# 05-AD8412.net
KiCad netlist of a schematic drawn in Altium Designer
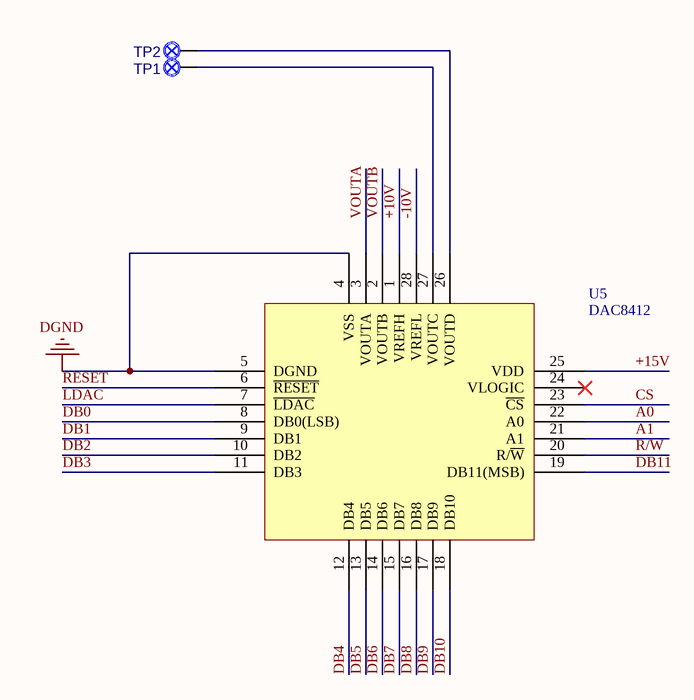
[diagram p0: 05-AD8412.SchDoc]

(export (version "E")
  (design (tool "Eeschema 10.0.6"))
  (components
    (comp (ref "TP1") (value "TESTPOINT") (footprint "TP24-SMD") (libsource (lib "*") (part "TESTPOINT_0")))
    (comp (ref "TP2") (value "TESTPOINT") (footprint "TP24-SMD") (libsource (lib "*") (part "TESTPOINT_0")))
    (comp (ref "U5")
      (value "DAC8412")
      (footprint "PLCC-28_L11.5-W11.5-P1.27-LS12.5-L")
      (libsource (lib "sucaiku") (part "DAC8412"))
    )
  )
  (nets
    (net (code "1") (name "/+10V") (class "Default")
      (node (ref "U5") (pin "1") (pinfunction "VREFH_1") (pintype "passive"))
    )
    (net (code "2") (name "/+15V") (class "Default")
      (node (ref "U5") (pin "25") (pinfunction "VDD_25") (pintype "passive"))
    )
    (net (code "3") (name "/-10V") (class "Default")
      (node (ref "U5") (pin "28") (pinfunction "VREFL_28") (pintype "passive"))
    )
    (net (code "4") (name "/A0") (class "Default")
      (node (ref "U5") (pin "22") (pinfunction "A0_22") (pintype "passive"))
    )
    (net (code "5") (name "/A1") (class "Default")
      (node (ref "U5") (pin "21") (pinfunction "A1_21") (pintype "passive"))
    )
    (net (code "6") (name "/CS") (class "Default")
      (node (ref "U5") (pin "23") (pinfunction "~{CS}_23") (pintype "passive"))
    )
    (net (code "7") (name "/DB0") (class "Default")
      (node (ref "U5") (pin "8") (pinfunction "DB0(LSB)_8") (pintype "passive"))
    )
    (net (code "8") (name "/DB1") (class "Default")
      (node (ref "U5") (pin "9") (pinfunction "DB1_9") (pintype "passive"))
    )
    (net (code "9") (name "/DB2") (class "Default")
      (node (ref "U5") (pin "10") (pinfunction "DB2_10") (pintype "passive"))
    )
    (net (code "10") (name "/DB3") (class "Default")
      (node (ref "U5") (pin "11") (pinfunction "DB3_11") (pintype "passive"))
    )
    (net (code "11") (name "/DB4") (class "Default")
      (node (ref "U5") (pin "12") (pinfunction "DB4_12") (pintype "passive"))
    )
    (net (code "12") (name "/DB5") (class "Default")
      (node (ref "U5") (pin "13") (pinfunction "DB5_13") (pintype "passive"))
    )
    (net (code "13") (name "/DB6") (class "Default")
      (node (ref "U5") (pin "14") (pinfunction "DB6_14") (pintype "passive"))
    )
    (net (code "14") (name "/DB7") (class "Default")
      (node (ref "U5") (pin "15") (pinfunction "DB7_15") (pintype "passive"))
    )
    (net (code "15") (name "/DB8") (class "Default")
      (node (ref "U5") (pin "16") (pinfunction "DB8_16") (pintype "passive"))
    )
    (net (code "16") (name "/DB9") (class "Default")
      (node (ref "U5") (pin "17") (pinfunction "DB9_17") (pintype "passive"))
    )
    (net (code "17") (name "/DB10") (class "Default")
      (node (ref "U5") (pin "18") (pinfunction "DB10_18") (pintype "passive"))
    )
    (net (code "18") (name "/DB11") (class "Default")
      (node (ref "U5") (pin "19") (pinfunction "DB11(MSB)_19") (pintype "passive"))
    )
    (net (code "19") (name "/LDAC") (class "Default")
      (node (ref "U5") (pin "7") (pinfunction "~{LDAC}_7") (pintype "passive"))
    )
    (net (code "20") (name "/RESET") (class "Default")
      (node (ref "U5") (pin "6") (pinfunction "~{RESET}_6") (pintype "passive"))
    )
    (net (code "21") (name "/R{slash}W") (class "Default")
      (node (ref "U5") (pin "20") (pinfunction "R/~{W}_20") (pintype "passive"))
    )
    (net (code "22") (name "/VOUTA") (class "Default")
      (node (ref "U5") (pin "3") (pinfunction "VOUTA_3") (pintype "passive"))
    )
    (net (code "23") (name "/VOUTB") (class "Default")
      (node (ref "U5") (pin "2") (pinfunction "VOUTB_2") (pintype "passive"))
    )
    (net (code "24") (name "DGND") (class "Default")
      (node (ref "U5") (pin "4") (pinfunction "VSS_4") (pintype "passive"))
      (node (ref "U5") (pin "5") (pinfunction "DGND_5") (pintype "passive"))
    )
    (net (code "25") (name "Net-(U5-VOUTC)") (class "Default")
      (node (ref "TP1") (pin "1") (pinfunction "1_1") (pintype "passive"))
      (node (ref "U5") (pin "27") (pinfunction "VOUTC_27") (pintype "passive"))
    )
    (net (code "26") (name "Net-(U5-VOUTD)") (class "Default")
      (node (ref "TP2") (pin "1") (pinfunction "1_1") (pintype "passive"))
      (node (ref "U5") (pin "26") (pinfunction "VOUTD_26") (pintype "passive"))
    )
    (net (code "27") (name "unconnected-(U5-VLOGIC-Pad24)") (class "Default")
      (node (ref "U5") (pin "24") (pinfunction "VLOGIC_24") (pintype "passive+no_connect"))
    )
  )
)
